# hub.net
KiCad netlist of a schematic drawn in EAGLE
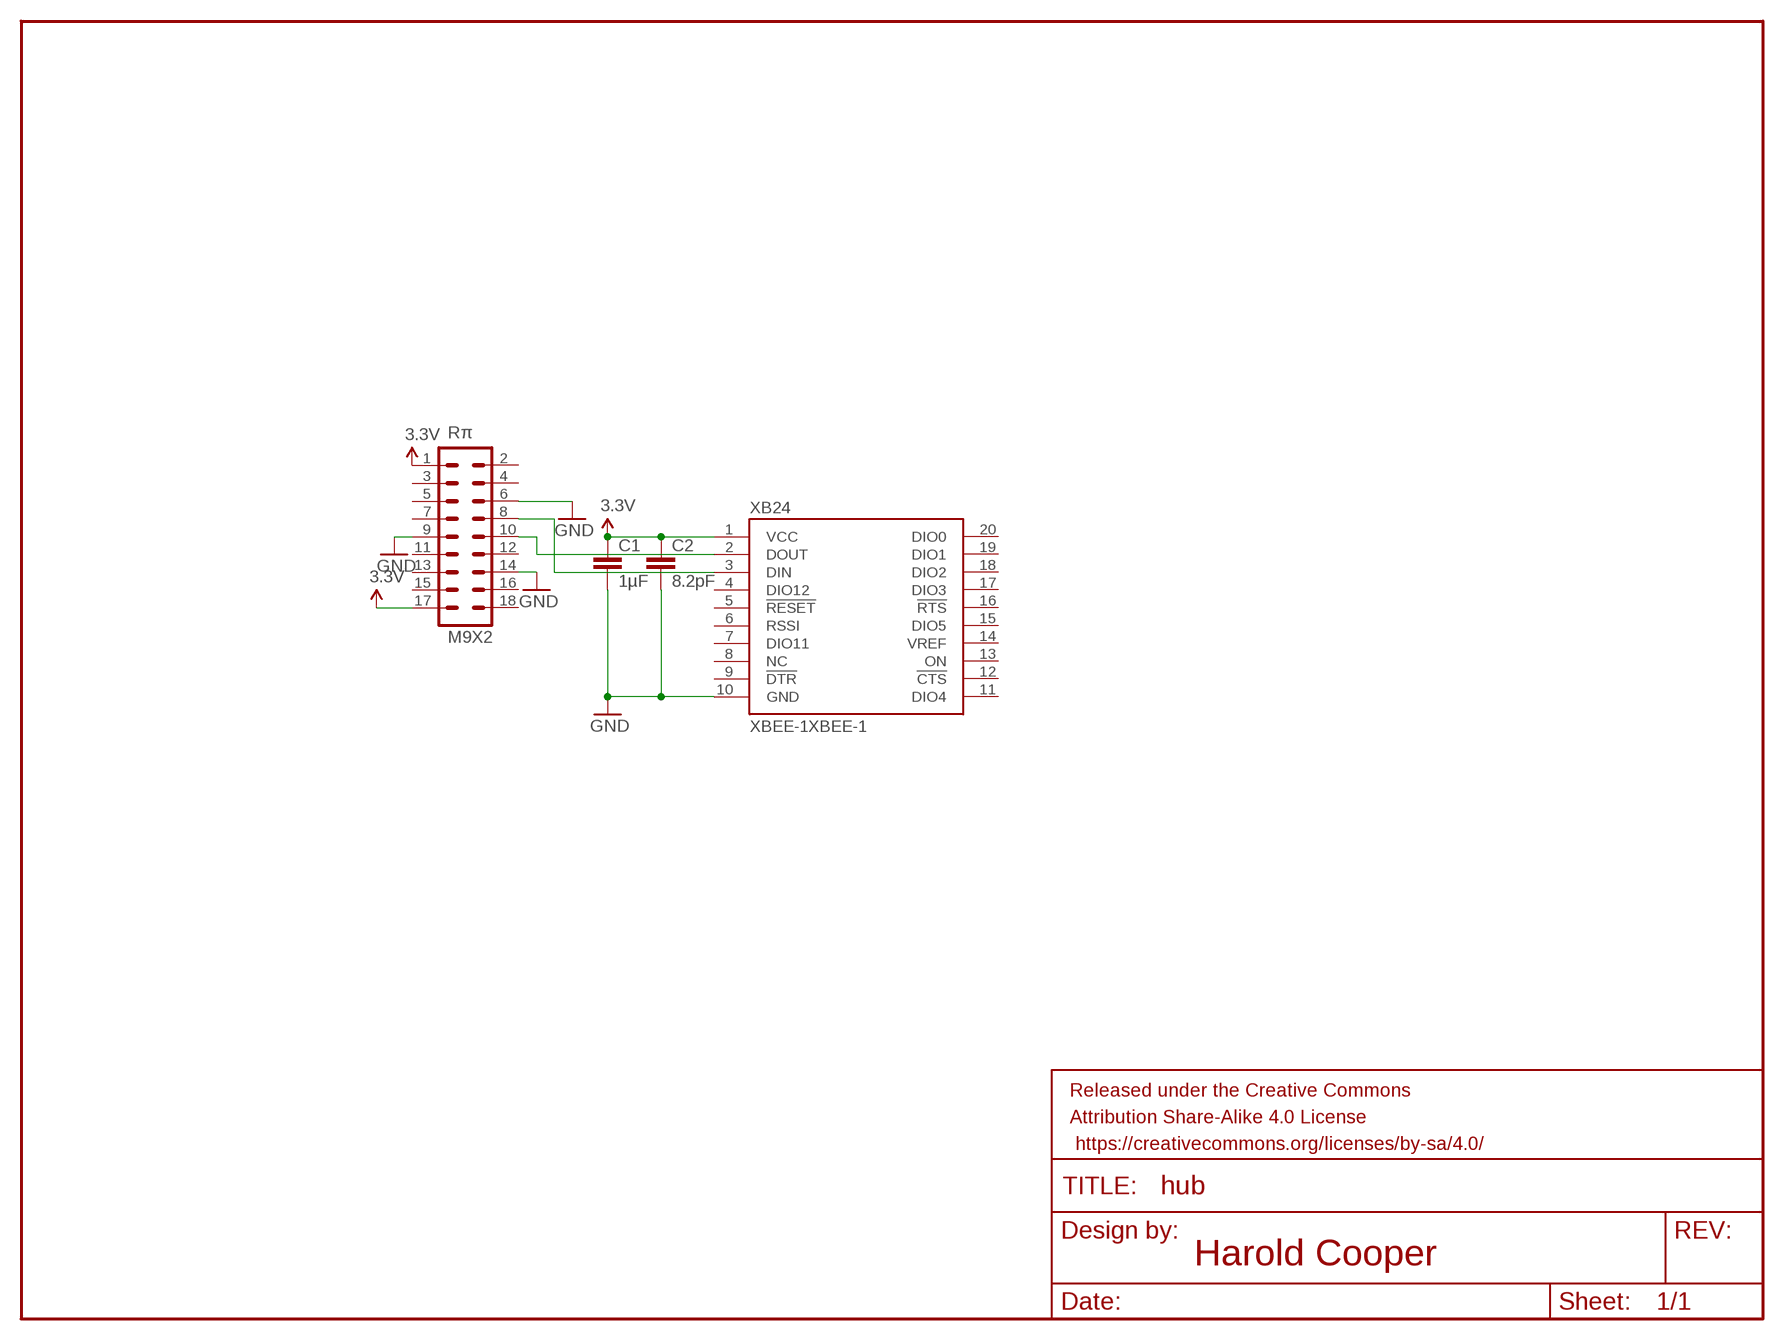
[diagram p0: schematic, sheet 1]

(export (version "E")
  (design (tool "Eeschema 10.0.6"))
  (components
    (comp (ref "C1")
      (value "1µF")
      (footprint "eagle-import:0805")
      (libsource (lib "eagle-import") (part "CAP0805"))
    )
    (comp (ref "C2")
      (value "8.2pF")
      (footprint "eagle-import:0805")
      (libsource (lib "eagle-import") (part "CAP0805"))
    )
    (comp (ref "FRAME1")
      (value "FRAME-LETTER")
      (footprint "eagle-import:CREATIVE_COMMONS")
      (libsource (lib "eagle-import") (part "FRAME-LETTER"))
    )
    (comp (ref "Rπ")
      (value "M9X2")
      (footprint "eagle-import:2X9_NOSILK")
      (libsource (lib "eagle-import") (part "M9X2"))
    )
    (comp (ref "XB24")
      (value "XBEE-1XBEE-1")
      (footprint "eagle-import:XBEE-1")
      (libsource (lib "eagle-import") (part "XBEE-1XBEE-1"))
    )
  )
  (nets
    (net (code "1") (name "/VREF") (class "Default")
      (node (ref "XB24") (pin "14") (pinfunction "VREF_14") (pintype "power_in"))
    )
    (net (code "2") (name "3.3V") (class "Default")
      (node (ref "C1") (pin "1") (pinfunction "1_1") (pintype "passive"))
      (node (ref "C2") (pin "1") (pinfunction "1_1") (pintype "passive"))
      (node (ref "Rπ") (pin "1") (pinfunction "1_1") (pintype "passive"))
      (node (ref "Rπ") (pin "17") (pinfunction "17_17") (pintype "passive"))
      (node (ref "XB24") (pin "1") (pinfunction "VCC_1") (pintype "power_in"))
    )
    (net (code "3") (name "GND") (class "Default")
      (node (ref "C1") (pin "2") (pinfunction "2_2") (pintype "passive"))
      (node (ref "C2") (pin "2") (pinfunction "2_2") (pintype "passive"))
      (node (ref "Rπ") (pin "14") (pinfunction "14_14") (pintype "passive"))
      (node (ref "Rπ") (pin "6") (pinfunction "6_6") (pintype "passive"))
      (node (ref "Rπ") (pin "9") (pinfunction "9_9") (pintype "passive"))
      (node (ref "XB24") (pin "10") (pinfunction "GND_10") (pintype "power_in"))
    )
    (net (code "4") (name "Net-(XB24-DIN)") (class "Default")
      (node (ref "Rπ") (pin "8") (pinfunction "8_8") (pintype "passive"))
      (node (ref "XB24") (pin "3") (pinfunction "DIN_3") (pintype "input"))
    )
    (net (code "5") (name "Net-(XB24-DOUT)") (class "Default")
      (node (ref "Rπ") (pin "10") (pinfunction "10_10") (pintype "passive"))
      (node (ref "XB24") (pin "2") (pinfunction "DOUT_2") (pintype "output"))
    )
    (net (code "6") (name "unconnected-(Rπ-Pad2)") (class "Default")
      (node (ref "Rπ") (pin "2") (pinfunction "2_2") (pintype "passive"))
    )
    (net (code "7") (name "unconnected-(Rπ-Pad3)") (class "Default")
      (node (ref "Rπ") (pin "3") (pinfunction "3_3") (pintype "passive"))
    )
    (net (code "8") (name "unconnected-(Rπ-Pad4)") (class "Default")
      (node (ref "Rπ") (pin "4") (pinfunction "4_4") (pintype "passive"))
    )
    (net (code "9") (name "unconnected-(Rπ-Pad5)") (class "Default")
      (node (ref "Rπ") (pin "5") (pinfunction "5_5") (pintype "passive"))
    )
    (net (code "10") (name "unconnected-(Rπ-Pad7)") (class "Default")
      (node (ref "Rπ") (pin "7") (pinfunction "7_7") (pintype "passive"))
    )
    (net (code "11") (name "unconnected-(Rπ-Pad11)") (class "Default")
      (node (ref "Rπ") (pin "11") (pinfunction "11_11") (pintype "passive"))
    )
    (net (code "12") (name "unconnected-(Rπ-Pad12)") (class "Default")
      (node (ref "Rπ") (pin "12") (pinfunction "12_12") (pintype "passive"))
    )
    (net (code "13") (name "unconnected-(Rπ-Pad13)") (class "Default")
      (node (ref "Rπ") (pin "13") (pinfunction "13_13") (pintype "passive"))
    )
    (net (code "14") (name "unconnected-(Rπ-Pad15)") (class "Default")
      (node (ref "Rπ") (pin "15") (pinfunction "15_15") (pintype "passive"))
    )
    (net (code "15") (name "unconnected-(Rπ-Pad16)") (class "Default")
      (node (ref "Rπ") (pin "16") (pinfunction "16_16") (pintype "passive"))
    )
    (net (code "16") (name "unconnected-(Rπ-Pad18)") (class "Default")
      (node (ref "Rπ") (pin "18") (pinfunction "18_18") (pintype "passive"))
    )
    (net (code "17") (name "unconnected-(XB24-DIO0-Pad20)") (class "Default")
      (node (ref "XB24") (pin "20") (pinfunction "DIO0_20") (pintype "bidirectional"))
    )
    (net (code "18") (name "unconnected-(XB24-DIO1-Pad19)") (class "Default")
      (node (ref "XB24") (pin "19") (pinfunction "DIO1_19") (pintype "bidirectional"))
    )
    (net (code "19") (name "unconnected-(XB24-DIO2-Pad18)") (class "Default")
      (node (ref "XB24") (pin "18") (pinfunction "DIO2_18") (pintype "bidirectional"))
    )
    (net (code "20") (name "unconnected-(XB24-DIO3-Pad17)") (class "Default")
      (node (ref "XB24") (pin "17") (pinfunction "DIO3_17") (pintype "bidirectional"))
    )
    (net (code "21") (name "unconnected-(XB24-DIO4-Pad11)") (class "Default")
      (node (ref "XB24") (pin "11") (pinfunction "DIO4_11") (pintype "bidirectional"))
    )
    (net (code "22") (name "unconnected-(XB24-DIO5-Pad15)") (class "Default")
      (node (ref "XB24") (pin "15") (pinfunction "DIO5_15") (pintype "bidirectional"))
    )
    (net (code "23") (name "unconnected-(XB24-DIO11-Pad7)") (class "Default")
      (node (ref "XB24") (pin "7") (pinfunction "DIO11_7") (pintype "bidirectional"))
    )
    (net (code "24") (name "unconnected-(XB24-DIO12-Pad4)") (class "Default")
      (node (ref "XB24") (pin "4") (pinfunction "DIO12_4") (pintype "bidirectional"))
    )
    (net (code "25") (name "unconnected-(XB24-NC-Pad8)") (class "Default")
      (node (ref "XB24") (pin "8") (pinfunction "NC_8") (pintype "no_connect"))
    )
    (net (code "26") (name "unconnected-(XB24-ON-Pad13)") (class "Default")
      (node (ref "XB24") (pin "13") (pinfunction "ON_13") (pintype "bidirectional"))
    )
    (net (code "27") (name "unconnected-(XB24-RSSI-Pad6)") (class "Default")
      (node (ref "XB24") (pin "6") (pinfunction "RSSI_6") (pintype "bidirectional"))
    )
    (net (code "28") (name "unconnected-(XB24-~{CTS}-Pad12)") (class "Default")
      (node (ref "XB24") (pin "12") (pinfunction "~{CTS}_12") (pintype "output"))
    )
    (net (code "29") (name "unconnected-(XB24-~{DTR}-Pad9)") (class "Default")
      (node (ref "XB24") (pin "9") (pinfunction "~{DTR}_9") (pintype "bidirectional"))
    )
    (net (code "30") (name "unconnected-(XB24-~{RESET}-Pad5)") (class "Default")
      (node (ref "XB24") (pin "5") (pinfunction "~{RESET}_5") (pintype "input"))
    )
    (net (code "31") (name "unconnected-(XB24-~{RTS}-Pad16)") (class "Default")
      (node (ref "XB24") (pin "16") (pinfunction "~{RTS}_16") (pintype "input"))
    )
  )
)
